# Connectors_pinout.net
KiCad netlist of a schematic drawn in Altium Designer
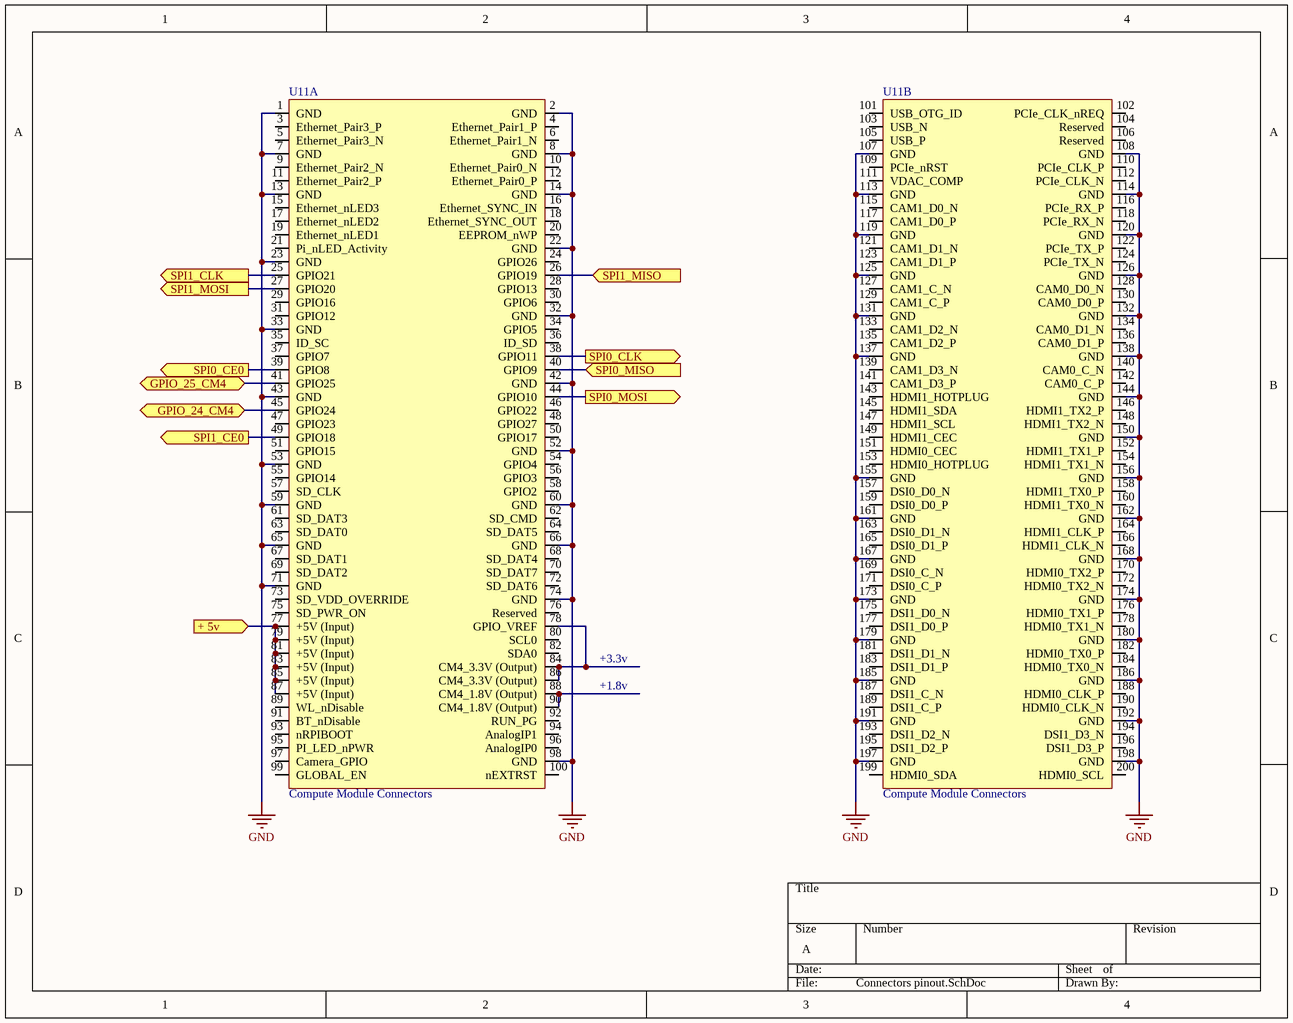
[diagram p0: Connectors pinout.SchDoc]

(export (version "E")
  (design (tool "Eeschema 10.0.6"))
  (components
    (comp (ref "U11")
      (value "Compute Module Connectors")
      (footprint "CM4-DF40HC(3.0)-100DS-0.4v_3mm_1.5mm_NO_Outline-3D")
      (libsource (lib "sch_comp") (part "Compute Module Connectors"))
    )
  )
  (nets
    (net (code "1") (name "/+ 5v") (class "Default")
      (node (ref "U11") (pin "77") (pinfunction "+5V_(Input)_77") (pintype "passive"))
      (node (ref "U11") (pin "79") (pinfunction "+5V_(Input)_79") (pintype "passive"))
      (node (ref "U11") (pin "81") (pinfunction "+5V_(Input)_81") (pintype "passive"))
      (node (ref "U11") (pin "83") (pinfunction "+5V_(Input)_83") (pintype "passive"))
      (node (ref "U11") (pin "85") (pinfunction "+5V_(Input)_85") (pintype "passive"))
      (node (ref "U11") (pin "87") (pinfunction "+5V_(Input)_87") (pintype "passive"))
    )
    (net (code "2") (name "/GPIO_24_CM4") (class "Default")
      (node (ref "U11") (pin "45") (pinfunction "GPIO24_45") (pintype "passive"))
    )
    (net (code "3") (name "/GPIO_25_CM4") (class "Default")
      (node (ref "U11") (pin "41") (pinfunction "GPIO25_41") (pintype "passive"))
    )
    (net (code "4") (name "/SPI0_CE0") (class "Default")
      (node (ref "U11") (pin "39") (pinfunction "GPIO8_39") (pintype "passive"))
    )
    (net (code "5") (name "/SPI0_CLK") (class "Default")
      (node (ref "U11") (pin "38") (pinfunction "GPIO11_38") (pintype "passive"))
    )
    (net (code "6") (name "/SPI0_MISO") (class "Default")
      (node (ref "U11") (pin "40") (pinfunction "GPIO9_40") (pintype "passive"))
    )
    (net (code "7") (name "/SPI0_MOSI") (class "Default")
      (node (ref "U11") (pin "44") (pinfunction "GPIO10_44") (pintype "passive"))
    )
    (net (code "8") (name "/SPI1_CE0") (class "Default")
      (node (ref "U11") (pin "49") (pinfunction "GPIO18_49") (pintype "passive"))
    )
    (net (code "9") (name "/SPI1_CLK") (class "Default")
      (node (ref "U11") (pin "25") (pinfunction "GPIO21_25") (pintype "passive"))
    )
    (net (code "10") (name "/SPI1_MISO") (class "Default")
      (node (ref "U11") (pin "26") (pinfunction "GPIO19_26") (pintype "passive"))
    )
    (net (code "11") (name "/SPI1_MOSI") (class "Default")
      (node (ref "U11") (pin "27") (pinfunction "GPIO20_27") (pintype "passive"))
    )
    (net (code "12") (name "GND") (class "Default")
      (node (ref "U11") (pin "1") (pinfunction "GND_1") (pintype "passive"))
      (node (ref "U11") (pin "107") (pinfunction "GND_107") (pintype "passive"))
      (node (ref "U11") (pin "108") (pinfunction "GND_108") (pintype "passive"))
      (node (ref "U11") (pin "113") (pinfunction "GND_113") (pintype "passive"))
      (node (ref "U11") (pin "114") (pinfunction "GND_114") (pintype "passive"))
      (node (ref "U11") (pin "119") (pinfunction "GND_119") (pintype "passive"))
      (node (ref "U11") (pin "120") (pinfunction "GND_120") (pintype "passive"))
      (node (ref "U11") (pin "125") (pinfunction "GND_125") (pintype "passive"))
      (node (ref "U11") (pin "126") (pinfunction "GND_126") (pintype "passive"))
      (node (ref "U11") (pin "13") (pinfunction "GND_13") (pintype "passive"))
      (node (ref "U11") (pin "131") (pinfunction "GND_131") (pintype "passive"))
      (node (ref "U11") (pin "132") (pinfunction "GND_132") (pintype "passive"))
      (node (ref "U11") (pin "137") (pinfunction "GND_137") (pintype "passive"))
      (node (ref "U11") (pin "138") (pinfunction "GND_138") (pintype "passive"))
      (node (ref "U11") (pin "14") (pinfunction "GND_14") (pintype "passive"))
      (node (ref "U11") (pin "144") (pinfunction "GND_144") (pintype "passive"))
      (node (ref "U11") (pin "150") (pinfunction "GND_150") (pintype "passive"))
      (node (ref "U11") (pin "155") (pinfunction "GND_155") (pintype "passive"))
      (node (ref "U11") (pin "156") (pinfunction "GND_156") (pintype "passive"))
      (node (ref "U11") (pin "161") (pinfunction "GND_161") (pintype "passive"))
      (node (ref "U11") (pin "162") (pinfunction "GND_162") (pintype "passive"))
      (node (ref "U11") (pin "167") (pinfunction "GND_167") (pintype "passive"))
      (node (ref "U11") (pin "168") (pinfunction "GND_168") (pintype "passive"))
      (node (ref "U11") (pin "173") (pinfunction "GND_173") (pintype "passive"))
      (node (ref "U11") (pin "174") (pinfunction "GND_174") (pintype "passive"))
      (node (ref "U11") (pin "179") (pinfunction "GND_179") (pintype "passive"))
      (node (ref "U11") (pin "180") (pinfunction "GND_180") (pintype "passive"))
      (node (ref "U11") (pin "185") (pinfunction "GND_185") (pintype "passive"))
      (node (ref "U11") (pin "186") (pinfunction "GND_186") (pintype "passive"))
      (node (ref "U11") (pin "191") (pinfunction "GND_191") (pintype "passive"))
      (node (ref "U11") (pin "192") (pinfunction "GND_192") (pintype "passive"))
      (node (ref "U11") (pin "197") (pinfunction "GND_197") (pintype "passive"))
      (node (ref "U11") (pin "198") (pinfunction "GND_198") (pintype "passive"))
      (node (ref "U11") (pin "2") (pinfunction "GND_2") (pintype "passive"))
      (node (ref "U11") (pin "22") (pinfunction "GND_22") (pintype "passive"))
      (node (ref "U11") (pin "23") (pinfunction "GND_23") (pintype "passive"))
      (node (ref "U11") (pin "32") (pinfunction "GND_32") (pintype "passive"))
      (node (ref "U11") (pin "33") (pinfunction "GND_33") (pintype "passive"))
      (node (ref "U11") (pin "42") (pinfunction "GND_42") (pintype "passive"))
      (node (ref "U11") (pin "43") (pinfunction "GND_43") (pintype "passive"))
      (node (ref "U11") (pin "52") (pinfunction "GND_52") (pintype "passive"))
      (node (ref "U11") (pin "53") (pinfunction "GND_53") (pintype "passive"))
      (node (ref "U11") (pin "59") (pinfunction "GND_59") (pintype "passive"))
      (node (ref "U11") (pin "60") (pinfunction "GND_60") (pintype "passive"))
      (node (ref "U11") (pin "65") (pinfunction "GND_65") (pintype "passive"))
      (node (ref "U11") (pin "66") (pinfunction "GND_66") (pintype "passive"))
      (node (ref "U11") (pin "7") (pinfunction "GND_7") (pintype "passive"))
      (node (ref "U11") (pin "71") (pinfunction "GND_71") (pintype "passive"))
      (node (ref "U11") (pin "74") (pinfunction "GND_74") (pintype "passive"))
      (node (ref "U11") (pin "8") (pinfunction "GND_8") (pintype "passive"))
      (node (ref "U11") (pin "98") (pinfunction "GND_98") (pintype "passive"))
    )
    (net (code "13") (name "Net-(U11A-CM4_1.8V_(Output)-Pad88)") (class "Default")
      (node (ref "U11") (pin "88") (pinfunction "CM4_1.8V_(Output)_88") (pintype "passive"))
      (node (ref "U11") (pin "90") (pinfunction "CM4_1.8V_(Output)_90") (pintype "passive"))
    )
    (net (code "14") (name "Net-(U11A-GPIO_VREF)") (class "Default")
      (node (ref "U11") (pin "78") (pinfunction "GPIO_VREF_78") (pintype "passive"))
      (node (ref "U11") (pin "84") (pinfunction "CM4_3.3V_(Output)_84") (pintype "passive"))
      (node (ref "U11") (pin "86") (pinfunction "CM4_3.3V_(Output)_86") (pintype "passive"))
    )
    (net (code "15") (name "unconnected-(U11A-AnalogIP0-Pad96)") (class "Default")
      (node (ref "U11") (pin "96") (pinfunction "AnalogIP0_96") (pintype "passive"))
    )
    (net (code "16") (name "unconnected-(U11A-AnalogIP1-Pad94)") (class "Default")
      (node (ref "U11") (pin "94") (pinfunction "AnalogIP1_94") (pintype "passive"))
    )
    (net (code "17") (name "unconnected-(U11A-BT_nDisable-Pad91)") (class "Default")
      (node (ref "U11") (pin "91") (pinfunction "BT_nDisable_91") (pintype "passive"))
    )
    (net (code "18") (name "unconnected-(U11A-Camera_GPIO-Pad97)") (class "Default")
      (node (ref "U11") (pin "97") (pinfunction "Camera_GPIO_97") (pintype "passive"))
    )
    (net (code "19") (name "unconnected-(U11A-EEPROM_nWP-Pad20)") (class "Default")
      (node (ref "U11") (pin "20") (pinfunction "EEPROM_nWP_20") (pintype "passive"))
    )
    (net (code "20") (name "unconnected-(U11A-Ethernet_Pair0_N-Pad10)") (class "Default")
      (node (ref "U11") (pin "10") (pinfunction "Ethernet_Pair0_N_10") (pintype "passive"))
    )
    (net (code "21") (name "unconnected-(U11A-Ethernet_Pair0_P-Pad12)") (class "Default")
      (node (ref "U11") (pin "12") (pinfunction "Ethernet_Pair0_P_12") (pintype "passive"))
    )
    (net (code "22") (name "unconnected-(U11A-Ethernet_Pair1_N-Pad6)") (class "Default")
      (node (ref "U11") (pin "6") (pinfunction "Ethernet_Pair1_N_6") (pintype "passive"))
    )
    (net (code "23") (name "unconnected-(U11A-Ethernet_Pair1_P-Pad4)") (class "Default")
      (node (ref "U11") (pin "4") (pinfunction "Ethernet_Pair1_P_4") (pintype "passive"))
    )
    (net (code "24") (name "unconnected-(U11A-Ethernet_Pair2_N-Pad9)") (class "Default")
      (node (ref "U11") (pin "9") (pinfunction "Ethernet_Pair2_N_9") (pintype "passive"))
    )
    (net (code "25") (name "unconnected-(U11A-Ethernet_Pair2_P-Pad11)") (class "Default")
      (node (ref "U11") (pin "11") (pinfunction "Ethernet_Pair2_P_11") (pintype "passive"))
    )
    (net (code "26") (name "unconnected-(U11A-Ethernet_Pair3_N-Pad5)") (class "Default")
      (node (ref "U11") (pin "5") (pinfunction "Ethernet_Pair3_N_5") (pintype "passive"))
    )
    (net (code "27") (name "unconnected-(U11A-Ethernet_Pair3_P-Pad3)") (class "Default")
      (node (ref "U11") (pin "3") (pinfunction "Ethernet_Pair3_P_3") (pintype "passive"))
    )
    (net (code "28") (name "unconnected-(U11A-Ethernet_SYNC_IN-Pad16)") (class "Default")
      (node (ref "U11") (pin "16") (pinfunction "Ethernet_SYNC_IN_16") (pintype "passive"))
    )
    (net (code "29") (name "unconnected-(U11A-Ethernet_SYNC_OUT-Pad18)") (class "Default")
      (node (ref "U11") (pin "18") (pinfunction "Ethernet_SYNC_OUT_18") (pintype "passive"))
    )
    (net (code "30") (name "unconnected-(U11A-Ethernet_nLED1-Pad19)") (class "Default")
      (node (ref "U11") (pin "19") (pinfunction "Ethernet_nLED1_19") (pintype "passive"))
    )
    (net (code "31") (name "unconnected-(U11A-Ethernet_nLED2-Pad17)") (class "Default")
      (node (ref "U11") (pin "17") (pinfunction "Ethernet_nLED2_17") (pintype "passive"))
    )
    (net (code "32") (name "unconnected-(U11A-Ethernet_nLED3-Pad15)") (class "Default")
      (node (ref "U11") (pin "15") (pinfunction "Ethernet_nLED3_15") (pintype "passive"))
    )
    (net (code "33") (name "unconnected-(U11A-GLOBAL_EN-Pad99)") (class "Default")
      (node (ref "U11") (pin "99") (pinfunction "GLOBAL_EN_99") (pintype "passive"))
    )
    (net (code "34") (name "unconnected-(U11A-GPIO2-Pad58)") (class "Default")
      (node (ref "U11") (pin "58") (pinfunction "GPIO2_58") (pintype "passive"))
    )
    (net (code "35") (name "unconnected-(U11A-GPIO3-Pad56)") (class "Default")
      (node (ref "U11") (pin "56") (pinfunction "GPIO3_56") (pintype "passive"))
    )
    (net (code "36") (name "unconnected-(U11A-GPIO4-Pad54)") (class "Default")
      (node (ref "U11") (pin "54") (pinfunction "GPIO4_54") (pintype "passive"))
    )
    (net (code "37") (name "unconnected-(U11A-GPIO5-Pad34)") (class "Default")
      (node (ref "U11") (pin "34") (pinfunction "GPIO5_34") (pintype "passive"))
    )
    (net (code "38") (name "unconnected-(U11A-GPIO6-Pad30)") (class "Default")
      (node (ref "U11") (pin "30") (pinfunction "GPIO6_30") (pintype "passive"))
    )
    (net (code "39") (name "unconnected-(U11A-GPIO7-Pad37)") (class "Default")
      (node (ref "U11") (pin "37") (pinfunction "GPIO7_37") (pintype "passive"))
    )
    (net (code "40") (name "unconnected-(U11A-GPIO12-Pad31)") (class "Default")
      (node (ref "U11") (pin "31") (pinfunction "GPIO12_31") (pintype "passive"))
    )
    (net (code "41") (name "unconnected-(U11A-GPIO13-Pad28)") (class "Default")
      (node (ref "U11") (pin "28") (pinfunction "GPIO13_28") (pintype "passive"))
    )
    (net (code "42") (name "unconnected-(U11A-GPIO14-Pad55)") (class "Default")
      (node (ref "U11") (pin "55") (pinfunction "GPIO14_55") (pintype "passive"))
    )
    (net (code "43") (name "unconnected-(U11A-GPIO15-Pad51)") (class "Default")
      (node (ref "U11") (pin "51") (pinfunction "GPIO15_51") (pintype "passive"))
    )
    (net (code "44") (name "unconnected-(U11A-GPIO16-Pad29)") (class "Default")
      (node (ref "U11") (pin "29") (pinfunction "GPIO16_29") (pintype "passive"))
    )
    (net (code "45") (name "unconnected-(U11A-GPIO17-Pad50)") (class "Default")
      (node (ref "U11") (pin "50") (pinfunction "GPIO17_50") (pintype "passive"))
    )
    (net (code "46") (name "unconnected-(U11A-GPIO22-Pad46)") (class "Default")
      (node (ref "U11") (pin "46") (pinfunction "GPIO22_46") (pintype "passive"))
    )
    (net (code "47") (name "unconnected-(U11A-GPIO23-Pad47)") (class "Default")
      (node (ref "U11") (pin "47") (pinfunction "GPIO23_47") (pintype "passive"))
    )
    (net (code "48") (name "unconnected-(U11A-GPIO26-Pad24)") (class "Default")
      (node (ref "U11") (pin "24") (pinfunction "GPIO26_24") (pintype "passive"))
    )
    (net (code "49") (name "unconnected-(U11A-GPIO27-Pad48)") (class "Default")
      (node (ref "U11") (pin "48") (pinfunction "GPIO27_48") (pintype "passive"))
    )
    (net (code "50") (name "unconnected-(U11A-ID_SC-Pad35)") (class "Default")
      (node (ref "U11") (pin "35") (pinfunction "ID_SC_35") (pintype "passive"))
    )
    (net (code "51") (name "unconnected-(U11A-ID_SD-Pad36)") (class "Default")
      (node (ref "U11") (pin "36") (pinfunction "ID_SD_36") (pintype "passive"))
    )
    (net (code "52") (name "unconnected-(U11A-PI_LED_nPWR-Pad95)") (class "Default")
      (node (ref "U11") (pin "95") (pinfunction "PI_LED_nPWR_95") (pintype "passive"))
    )
    (net (code "53") (name "unconnected-(U11A-Pi_nLED_Activity-Pad21)") (class "Default")
      (node (ref "U11") (pin "21") (pinfunction "Pi_nLED_Activity_21") (pintype "passive"))
    )
    (net (code "54") (name "unconnected-(U11A-RUN_PG-Pad92)") (class "Default")
      (node (ref "U11") (pin "92") (pinfunction "RUN_PG_92") (pintype "passive"))
    )
    (net (code "55") (name "unconnected-(U11A-Reserved-Pad76)") (class "Default")
      (node (ref "U11") (pin "76") (pinfunction "Reserved_76") (pintype "passive"))
    )
    (net (code "56") (name "unconnected-(U11A-SCL0-Pad80)") (class "Default")
      (node (ref "U11") (pin "80") (pinfunction "SCL0_80") (pintype "passive"))
    )
    (net (code "57") (name "unconnected-(U11A-SDA0-Pad82)") (class "Default")
      (node (ref "U11") (pin "82") (pinfunction "SDA0_82") (pintype "passive"))
    )
    (net (code "58") (name "unconnected-(U11A-SD_CLK-Pad57)") (class "Default")
      (node (ref "U11") (pin "57") (pinfunction "SD_CLK_57") (pintype "passive"))
    )
    (net (code "59") (name "unconnected-(U11A-SD_CMD-Pad62)") (class "Default")
      (node (ref "U11") (pin "62") (pinfunction "SD_CMD_62") (pintype "passive"))
    )
    (net (code "60") (name "unconnected-(U11A-SD_DAT0-Pad63)") (class "Default")
      (node (ref "U11") (pin "63") (pinfunction "SD_DAT0_63") (pintype "passive"))
    )
    (net (code "61") (name "unconnected-(U11A-SD_DAT1-Pad67)") (class "Default")
      (node (ref "U11") (pin "67") (pinfunction "SD_DAT1_67") (pintype "passive"))
    )
    (net (code "62") (name "unconnected-(U11A-SD_DAT2-Pad69)") (class "Default")
      (node (ref "U11") (pin "69") (pinfunction "SD_DAT2_69") (pintype "passive"))
    )
    (net (code "63") (name "unconnected-(U11A-SD_DAT3-Pad61)") (class "Default")
      (node (ref "U11") (pin "61") (pinfunction "SD_DAT3_61") (pintype "passive"))
    )
    (net (code "64") (name "unconnected-(U11A-SD_DAT4-Pad68)") (class "Default")
      (node (ref "U11") (pin "68") (pinfunction "SD_DAT4_68") (pintype "passive"))
    )
    (net (code "65") (name "unconnected-(U11A-SD_DAT5-Pad64)") (class "Default")
      (node (ref "U11") (pin "64") (pinfunction "SD_DAT5_64") (pintype "passive"))
    )
    (net (code "66") (name "unconnected-(U11A-SD_DAT6-Pad72)") (class "Default")
      (node (ref "U11") (pin "72") (pinfunction "SD_DAT6_72") (pintype "passive"))
    )
    (net (code "67") (name "unconnected-(U11A-SD_DAT7-Pad70)") (class "Default")
      (node (ref "U11") (pin "70") (pinfunction "SD_DAT7_70") (pintype "passive"))
    )
    (net (code "68") (name "unconnected-(U11A-SD_PWR_ON-Pad75)") (class "Default")
      (node (ref "U11") (pin "75") (pinfunction "SD_PWR_ON_75") (pintype "passive"))
    )
    (net (code "69") (name "unconnected-(U11A-SD_VDD_OVERRIDE-Pad73)") (class "Default")
      (node (ref "U11") (pin "73") (pinfunction "SD_VDD_OVERRIDE_73") (pintype "passive"))
    )
    (net (code "70") (name "unconnected-(U11A-WL_nDisable-Pad89)") (class "Default")
      (node (ref "U11") (pin "89") (pinfunction "WL_nDisable_89") (pintype "passive"))
    )
    (net (code "71") (name "unconnected-(U11A-nEXTRST-Pad100)") (class "Default")
      (node (ref "U11") (pin "100") (pinfunction "nEXTRST_100") (pintype "passive"))
    )
    (net (code "72") (name "unconnected-(U11A-nRPIBOOT-Pad93)") (class "Default")
      (node (ref "U11") (pin "93") (pinfunction "nRPIBOOT_93") (pintype "passive"))
    )
    (net (code "73") (name "unconnected-(U11B-CAM0_C_N-Pad140)") (class "Default")
      (node (ref "U11") (pin "140") (pinfunction "CAM0_C_N_140") (pintype "passive"))
    )
    (net (code "74") (name "unconnected-(U11B-CAM0_C_P-Pad142)") (class "Default")
      (node (ref "U11") (pin "142") (pinfunction "CAM0_C_P_142") (pintype "passive"))
    )
    (net (code "75") (name "unconnected-(U11B-CAM0_D0_N-Pad128)") (class "Default")
      (node (ref "U11") (pin "128") (pinfunction "CAM0_D0_N_128") (pintype "passive"))
    )
    (net (code "76") (name "unconnected-(U11B-CAM0_D0_P-Pad130)") (class "Default")
      (node (ref "U11") (pin "130") (pinfunction "CAM0_D0_P_130") (pintype "passive"))
    )
    (net (code "77") (name "unconnected-(U11B-CAM0_D1_N-Pad134)") (class "Default")
      (node (ref "U11") (pin "134") (pinfunction "CAM0_D1_N_134") (pintype "passive"))
    )
    (net (code "78") (name "unconnected-(U11B-CAM0_D1_P-Pad136)") (class "Default")
      (node (ref "U11") (pin "136") (pinfunction "CAM0_D1_P_136") (pintype "passive"))
    )
    (net (code "79") (name "unconnected-(U11B-CAM1_C_N-Pad127)") (class "Default")
      (node (ref "U11") (pin "127") (pinfunction "CAM1_C_N_127") (pintype "passive"))
    )
    (net (code "80") (name "unconnected-(U11B-CAM1_C_P-Pad129)") (class "Default")
      (node (ref "U11") (pin "129") (pinfunction "CAM1_C_P_129") (pintype "passive"))
    )
    (net (code "81") (name "unconnected-(U11B-CAM1_D0_N-Pad115)") (class "Default")
      (node (ref "U11") (pin "115") (pinfunction "CAM1_D0_N_115") (pintype "passive"))
    )
    (net (code "82") (name "unconnected-(U11B-CAM1_D0_P-Pad117)") (class "Default")
      (node (ref "U11") (pin "117") (pinfunction "CAM1_D0_P_117") (pintype "passive"))
    )
    (net (code "83") (name "unconnected-(U11B-CAM1_D1_N-Pad121)") (class "Default")
      (node (ref "U11") (pin "121") (pinfunction "CAM1_D1_N_121") (pintype "passive"))
    )
    (net (code "84") (name "unconnected-(U11B-CAM1_D1_P-Pad123)") (class "Default")
      (node (ref "U11") (pin "123") (pinfunction "CAM1_D1_P_123") (pintype "passive"))
    )
    (net (code "85") (name "unconnected-(U11B-CAM1_D2_N-Pad133)") (class "Default")
      (node (ref "U11") (pin "133") (pinfunction "CAM1_D2_N_133") (pintype "passive"))
    )
    (net (code "86") (name "unconnected-(U11B-CAM1_D2_P-Pad135)") (class "Default")
      (node (ref "U11") (pin "135") (pinfunction "CAM1_D2_P_135") (pintype "passive"))
    )
    (net (code "87") (name "unconnected-(U11B-CAM1_D3_N-Pad139)") (class "Default")
      (node (ref "U11") (pin "139") (pinfunction "CAM1_D3_N_139") (pintype "passive"))
    )
    (net (code "88") (name "unconnected-(U11B-CAM1_D3_P-Pad141)") (class "Default")
      (node (ref "U11") (pin "141") (pinfunction "CAM1_D3_P_141") (pintype "passive"))
    )
    (net (code "89") (name "unconnected-(U11B-DSI0_C_N-Pad169)") (class "Default")
      (node (ref "U11") (pin "169") (pinfunction "DSI0_C_N_169") (pintype "passive"))
    )
    (net (code "90") (name "unconnected-(U11B-DSI0_C_P-Pad171)") (class "Default")
      (node (ref "U11") (pin "171") (pinfunction "DSI0_C_P_171") (pintype "passive"))
    )
    (net (code "91") (name "unconnected-(U11B-DSI0_D0_N-Pad157)") (class "Default")
      (node (ref "U11") (pin "157") (pinfunction "DSI0_D0_N_157") (pintype "passive"))
    )
    (net (code "92") (name "unconnected-(U11B-DSI0_D0_P-Pad159)") (class "Default")
      (node (ref "U11") (pin "159") (pinfunction "DSI0_D0_P_159") (pintype "passive"))
    )
    (net (code "93") (name "unconnected-(U11B-DSI0_D1_N-Pad163)") (class "Default")
      (node (ref "U11") (pin "163") (pinfunction "DSI0_D1_N_163") (pintype "passive"))
    )
    (net (code "94") (name "unconnected-(U11B-DSI0_D1_P-Pad165)") (class "Default")
      (node (ref "U11") (pin "165") (pinfunction "DSI0_D1_P_165") (pintype "passive"))
    )
    (net (code "95") (name "unconnected-(U11B-DSI1_C_N-Pad187)") (class "Default")
      (node (ref "U11") (pin "187") (pinfunction "DSI1_C_N_187") (pintype "passive"))
    )
    (net (code "96") (name "unconnected-(U11B-DSI1_C_P-Pad189)") (class "Default")
      (node (ref "U11") (pin "189") (pinfunction "DSI1_C_P_189") (pintype "passive"))
    )
    (net (code "97") (name "unconnected-(U11B-DSI1_D0_N-Pad175)") (class "Default")
      (node (ref "U11") (pin "175") (pinfunction "DSI1_D0_N_175") (pintype "passive"))
    )
    (net (code "98") (name "unconnected-(U11B-DSI1_D0_P-Pad177)") (class "Default")
      (node (ref "U11") (pin "177") (pinfunction "DSI1_D0_P_177") (pintype "passive"))
    )
    (net (code "99") (name "unconnected-(U11B-DSI1_D1_N-Pad181)") (class "Default")
      (node (ref "U11") (pin "181") (pinfunction "DSI1_D1_N_181") (pintype "passive"))
    )
    (net (code "100") (name "unconnected-(U11B-DSI1_D1_P-Pad183)") (class "Default")
      (node (ref "U11") (pin "183") (pinfunction "DSI1_D1_P_183") (pintype "passive"))
    )
    (net (code "101") (name "unconnected-(U11B-DSI1_D2_N-Pad193)") (class "Default")
      (node (ref "U11") (pin "193") (pinfunction "DSI1_D2_N_193") (pintype "passive"))
    )
    (net (code "102") (name "unconnected-(U11B-DSI1_D2_P-Pad195)") (class "Default")
      (node (ref "U11") (pin "195") (pinfunction "DSI1_D2_P_195") (pintype "passive"))
    )
    (net (code "103") (name "unconnected-(U11B-DSI1_D3_N-Pad194)") (class "Default")
      (node (ref "U11") (pin "194") (pinfunction "DSI1_D3_N_194") (pintype "passive"))
    )
    (net (code "104") (name "unconnected-(U11B-DSI1_D3_P-Pad196)") (class "Default")
      (node (ref "U11") (pin "196") (pinfunction "DSI1_D3_P_196") (pintype "passive"))
    )
    (net (code "105") (name "unconnected-(U11B-HDMI0_CEC-Pad151)") (class "Default")
      (node (ref "U11") (pin "151") (pinfunction "HDMI0_CEC_151") (pintype "passive"))
    )
    (net (code "106") (name "unconnected-(U11B-HDMI0_CLK_N-Pad190)") (class "Default")
      (node (ref "U11") (pin "190") (pinfunction "HDMI0_CLK_N_190") (pintype "passive"))
    )
    (net (code "107") (name "unconnected-(U11B-HDMI0_CLK_P-Pad188)") (class "Default")
      (node (ref "U11") (pin "188") (pinfunction "HDMI0_CLK_P_188") (pintype "passive"))
    )
    (net (code "108") (name "unconnected-(U11B-HDMI0_HOTPLUG-Pad153)") (class "Default")
      (node (ref "U11") (pin "153") (pinfunction "HDMI0_HOTPLUG_153") (pintype "passive"))
    )
    (net (code "109") (name "unconnected-(U11B-HDMI0_SCL-Pad200)") (class "Default")
      (node (ref "U11") (pin "200") (pinfunction "HDMI0_SCL_200") (pintype "passive"))
    )
    (net (code "110") (name "unconnected-(U11B-HDMI0_SDA-Pad199)") (class "Default")
      (node (ref "U11") (pin "199") (pinfunction "HDMI0_SDA_199") (pintype "passive"))
    )
    (net (code "111") (name "unconnected-(U11B-HDMI0_TX0_N-Pad184)") (class "Default")
      (node (ref "U11") (pin "184") (pinfunction "HDMI0_TX0_N_184") (pintype "passive"))
    )
    (net (code "112") (name "unconnected-(U11B-HDMI0_TX0_P-Pad182)") (class "Default")
      (node (ref "U11") (pin "182") (pinfunction "HDMI0_TX0_P_182") (pintype "passive"))
    )
    (net (code "113") (name "unconnected-(U11B-HDMI0_TX1_N-Pad178)") (class "Default")
      (node (ref "U11") (pin "178") (pinfunction "HDMI0_TX1_N_178") (pintype "passive"))
    )
    (net (code "114") (name "unconnected-(U11B-HDMI0_TX1_P-Pad176)") (class "Default")
      (node (ref "U11") (pin "176") (pinfunction "HDMI0_TX1_P_176") (pintype "passive"))
    )
    (net (code "115") (name "unconnected-(U11B-HDMI0_TX2_N-Pad172)") (class "Default")
      (node (ref "U11") (pin "172") (pinfunction "HDMI0_TX2_N_172") (pintype "passive"))
    )
    (net (code "116") (name "unconnected-(U11B-HDMI0_TX2_P-Pad170)") (class "Default")
      (node (ref "U11") (pin "170") (pinfunction "HDMI0_TX2_P_170") (pintype "passive"))
    )
    (net (code "117") (name "unconnected-(U11B-HDMI1_CEC-Pad149)") (class "Default")
      (node (ref "U11") (pin "149") (pinfunction "HDMI1_CEC_149") (pintype "passive"))
    )
    (net (code "118") (name "unconnected-(U11B-HDMI1_CLK_N-Pad166)") (class "Default")
      (node (ref "U11") (pin "166") (pinfunction "HDMI1_CLK_N_166") (pintype "passive"))
    )
    (net (code "119") (name "unconnected-(U11B-HDMI1_CLK_P-Pad164)") (class "Default")
      (node (ref "U11") (pin "164") (pinfunction "HDMI1_CLK_P_164") (pintype "passive"))
    )
    (net (code "120") (name "unconnected-(U11B-HDMI1_HOTPLUG-Pad143)") (class "Default")
      (node (ref "U11") (pin "143") (pinfunction "HDMI1_HOTPLUG_143") (pintype "passive"))
    )
    (net (code "121") (name "unconnected-(U11B-HDMI1_SCL-Pad147)") (class "Default")
      (node (ref "U11") (pin "147") (pinfunction "HDMI1_SCL_147") (pintype "passive"))
    )
    (net (code "122") (name "unconnected-(U11B-HDMI1_SDA-Pad145)") (class "Default")
      (node (ref "U11") (pin "145") (pinfunction "HDMI1_SDA_145") (pintype "passive"))
    )
    (net (code "123") (name "unconnected-(U11B-HDMI1_TX0_N-Pad160)") (class "Default")
      (node (ref "U11") (pin "160") (pinfunction "HDMI1_TX0_N_160") (pintype "passive"))
    )
    (net (code "124") (name "unconnected-(U11B-HDMI1_TX0_P-Pad158)") (class "Default")
      (node (ref "U11") (pin "158") (pinfunction "HDMI1_TX0_P_158") (pintype "passive"))
    )
    (net (code "125") (name "unconnected-(U11B-HDMI1_TX1_N-Pad154)") (class "Default")
      (node (ref "U11") (pin "154") (pinfunction "HDMI1_TX1_N_154") (pintype "passive"))
    )
    (net (code "126") (name "unconnected-(U11B-HDMI1_TX1_P-Pad152)") (class "Default")
      (node (ref "U11") (pin "152") (pinfunction "HDMI1_TX1_P_152") (pintype "passive"))
    )
    (net (code "127") (name "unconnected-(U11B-HDMI1_TX2_N-Pad148)") (class "Default")
      (node (ref "U11") (pin "148") (pinfunction "HDMI1_TX2_N_148") (pintype "passive"))
    )
    (net (code "128") (name "unconnected-(U11B-HDMI1_TX2_P-Pad146)") (class "Default")
      (node (ref "U11") (pin "146") (pinfunction "HDMI1_TX2_P_146") (pintype "passive"))
    )
    (net (code "129") (name "unconnected-(U11B-PCIe_CLK_N-Pad112)") (class "Default")
      (node (ref "U11") (pin "112") (pinfunction "PCIe_CLK_N_112") (pintype "passive"))
    )
    (net (code "130") (name "unconnected-(U11B-PCIe_CLK_P-Pad110)") (class "Default")
      (node (ref "U11") (pin "110") (pinfunction "PCIe_CLK_P_110") (pintype "passive"))
    )
    (net (code "131") (name "unconnected-(U11B-PCIe_CLK_nREQ-Pad102)") (class "Default")
      (node (ref "U11") (pin "102") (pinfunction "PCIe_CLK_nREQ_102") (pintype "passive"))
    )
    (net (code "132") (name "unconnected-(U11B-PCIe_RX_N-Pad118)") (class "Default")
      (node (ref "U11") (pin "118") (pinfunction "PCIe_RX_N_118") (pintype "passive"))
    )
    (net (code "133") (name "unconnected-(U11B-PCIe_RX_P-Pad116)") (class "Default")
      (node (ref "U11") (pin "116") (pinfunction "PCIe_RX_P_116") (pintype "passive"))
    )
    (net (code "134") (name "unconnected-(U11B-PCIe_TX_N-Pad124)") (class "Default")
      (node (ref "U11") (pin "124") (pinfunction "PCIe_TX_N_124") (pintype "passive"))
    )
    (net (code "135") (name "unconnected-(U11B-PCIe_TX_P-Pad122)") (class "Default")
      (node (ref "U11") (pin "122") (pinfunction "PCIe_TX_P_122") (pintype "passive"))
    )
    (net (code "136") (name "unconnected-(U11B-PCIe_nRST-Pad109)") (class "Default")
      (node (ref "U11") (pin "109") (pinfunction "PCIe_nRST_109") (pintype "passive"))
    )
    (net (code "137") (name "unconnected-(U11B-Reserved-Pad104)") (class "Default")
      (node (ref "U11") (pin "104") (pinfunction "Reserved_104") (pintype "passive"))
    )
    (net (code "138") (name "unconnected-(U11B-Reserved-Pad106)") (class "Default")
      (node (ref "U11") (pin "106") (pinfunction "Reserved_106") (pintype "passive"))
    )
    (net (code "139") (name "unconnected-(U11B-USB_N-Pad103)") (class "Default")
      (node (ref "U11") (pin "103") (pinfunction "USB_N_103") (pintype "passive"))
    )
    (net (code "140") (name "unconnected-(U11B-USB_OTG_ID-Pad101)") (class "Default")
      (node (ref "U11") (pin "101") (pinfunction "USB_OTG_ID_101") (pintype "passive"))
    )
    (net (code "141") (name "unconnected-(U11B-USB_P-Pad105)") (class "Default")
      (node (ref "U11") (pin "105") (pinfunction "USB_P_105") (pintype "passive"))
    )
    (net (code "142") (name "unconnected-(U11B-VDAC_COMP-Pad111)") (class "Default")
      (node (ref "U11") (pin "111") (pinfunction "VDAC_COMP_111") (pintype "passive"))
    )
  )
)
